# sup_cap_RC_circuit.net
KiCad netlist of a schematic drawn in Altium Designer
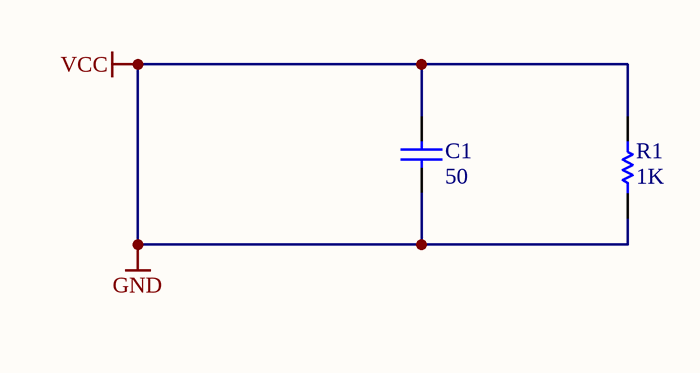
[diagram p0: sup_cap_RC circuit.SchDoc]

(export (version "E")
  (design (tool "Eeschema 10.0.6"))
  (components
    (comp (ref "C1")
      (value "50")
      (description "Capacitor")
      (libsource (lib "Simulation Generic Components") (part "Capacitor"))
    )
    (comp (ref "R1")
      (value "1K")
      (description "Resistor")
      (libsource (lib "Simulation Generic Components") (part "Resistor"))
    )
  )
  (nets
    (net (code "1") (name "GND") (class "Default")
      (node (ref "C1") (pin "1") (pinfunction "1_1") (pintype "passive"))
      (node (ref "C1") (pin "2") (pinfunction "2_2") (pintype "passive"))
      (node (ref "R1") (pin "1") (pinfunction "1_1") (pintype "passive"))
      (node (ref "R1") (pin "2") (pinfunction "2_2") (pintype "passive"))
    )
  )
)
